# cd4051.net
KiCad netlist of a schematic drawn in EAGLE
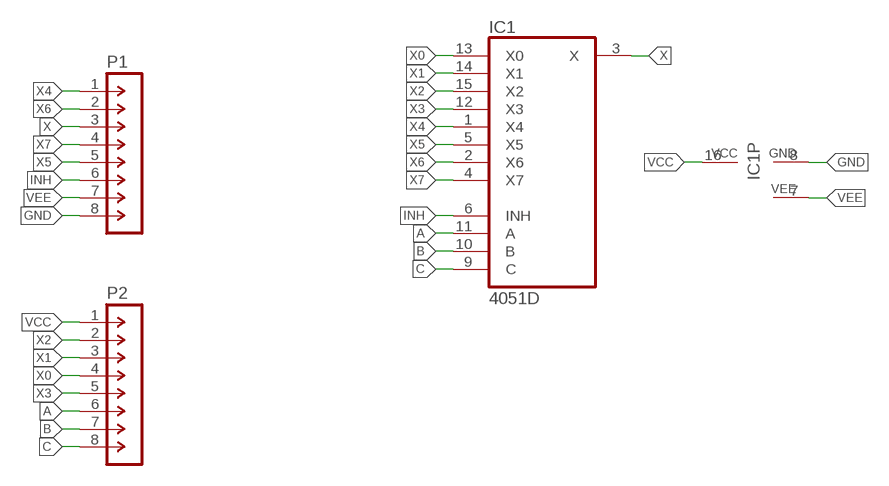
[diagram p0: schematic, sheet 1]

(export (version "E")
  (design (tool "Eeschema 10.0.6"))
  (components
    (comp (ref "IC1")
      (value "4051D")
      (footprint "eagle-import:SO16")
      (libsource (lib "eagle-import") (part "4051D"))
    )
    (comp (ref "P1")
      (value "M-1X08-SIP-100-32Y")
      (footprint "eagle-import:SIP-100-08-32Y")
      (libsource (lib "eagle-import") (part "M-1X08-SIP-100-32Y"))
    )
    (comp (ref "P2")
      (value "M-1X08-SIP-100-32Y")
      (footprint "eagle-import:SIP-100-08-32Y")
      (libsource (lib "eagle-import") (part "M-1X08-SIP-100-32Y"))
    )
  )
  (nets
    (net (code "1") (name "A") (class "Default")
      (node (ref "IC1") (pin "11") (pinfunction "A_11") (pintype "input"))
      (node (ref "P2") (pin "6") (pinfunction "6_6") (pintype "passive"))
    )
    (net (code "2") (name "B") (class "Default")
      (node (ref "IC1") (pin "10") (pinfunction "B_10") (pintype "input"))
      (node (ref "P2") (pin "7") (pinfunction "7_7") (pintype "passive"))
    )
    (net (code "3") (name "C") (class "Default")
      (node (ref "IC1") (pin "9") (pinfunction "C_9") (pintype "input"))
      (node (ref "P2") (pin "8") (pinfunction "8_8") (pintype "passive"))
    )
    (net (code "4") (name "GND") (class "Default")
      (node (ref "IC1") (pin "8") (pinfunction "GND_8") (pintype "power_in"))
      (node (ref "P1") (pin "8") (pinfunction "8_8") (pintype "passive"))
    )
    (net (code "5") (name "INH") (class "Default")
      (node (ref "IC1") (pin "6") (pinfunction "INH_6") (pintype "input"))
      (node (ref "P1") (pin "6") (pinfunction "6_6") (pintype "passive"))
    )
    (net (code "6") (name "VCC") (class "Default")
      (node (ref "IC1") (pin "16") (pinfunction "VCC_16") (pintype "power_in"))
      (node (ref "P2") (pin "1") (pinfunction "1_1") (pintype "passive"))
    )
    (net (code "7") (name "VEE") (class "Default")
      (node (ref "IC1") (pin "7") (pinfunction "VEE_7") (pintype "power_in"))
      (node (ref "P1") (pin "7") (pinfunction "7_7") (pintype "passive"))
    )
    (net (code "8") (name "X") (class "Default")
      (node (ref "IC1") (pin "3") (pinfunction "X_3") (pintype "bidirectional"))
      (node (ref "P1") (pin "3") (pinfunction "3_3") (pintype "passive"))
    )
    (net (code "9") (name "X0") (class "Default")
      (node (ref "IC1") (pin "13") (pinfunction "X0_13") (pintype "bidirectional"))
      (node (ref "P2") (pin "4") (pinfunction "4_4") (pintype "passive"))
    )
    (net (code "10") (name "X1") (class "Default")
      (node (ref "IC1") (pin "14") (pinfunction "X1_14") (pintype "bidirectional"))
      (node (ref "P2") (pin "3") (pinfunction "3_3") (pintype "passive"))
    )
    (net (code "11") (name "X2") (class "Default")
      (node (ref "IC1") (pin "15") (pinfunction "X2_15") (pintype "bidirectional"))
      (node (ref "P2") (pin "2") (pinfunction "2_2") (pintype "passive"))
    )
    (net (code "12") (name "X3") (class "Default")
      (node (ref "IC1") (pin "12") (pinfunction "X3_12") (pintype "bidirectional"))
      (node (ref "P2") (pin "5") (pinfunction "5_5") (pintype "passive"))
    )
    (net (code "13") (name "X4") (class "Default")
      (node (ref "IC1") (pin "1") (pinfunction "X4_1") (pintype "bidirectional"))
      (node (ref "P1") (pin "1") (pinfunction "1_1") (pintype "passive"))
    )
    (net (code "14") (name "X5") (class "Default")
      (node (ref "IC1") (pin "5") (pinfunction "X5_5") (pintype "bidirectional"))
      (node (ref "P1") (pin "5") (pinfunction "5_5") (pintype "passive"))
    )
    (net (code "15") (name "X6") (class "Default")
      (node (ref "IC1") (pin "2") (pinfunction "X6_2") (pintype "bidirectional"))
      (node (ref "P1") (pin "2") (pinfunction "2_2") (pintype "passive"))
    )
    (net (code "16") (name "X7") (class "Default")
      (node (ref "IC1") (pin "4") (pinfunction "X7_4") (pintype "bidirectional"))
      (node (ref "P1") (pin "4") (pinfunction "4_4") (pintype "passive"))
    )
  )
)
